# chest_07_15_2017.net
KiCad netlist of a schematic drawn in EAGLE
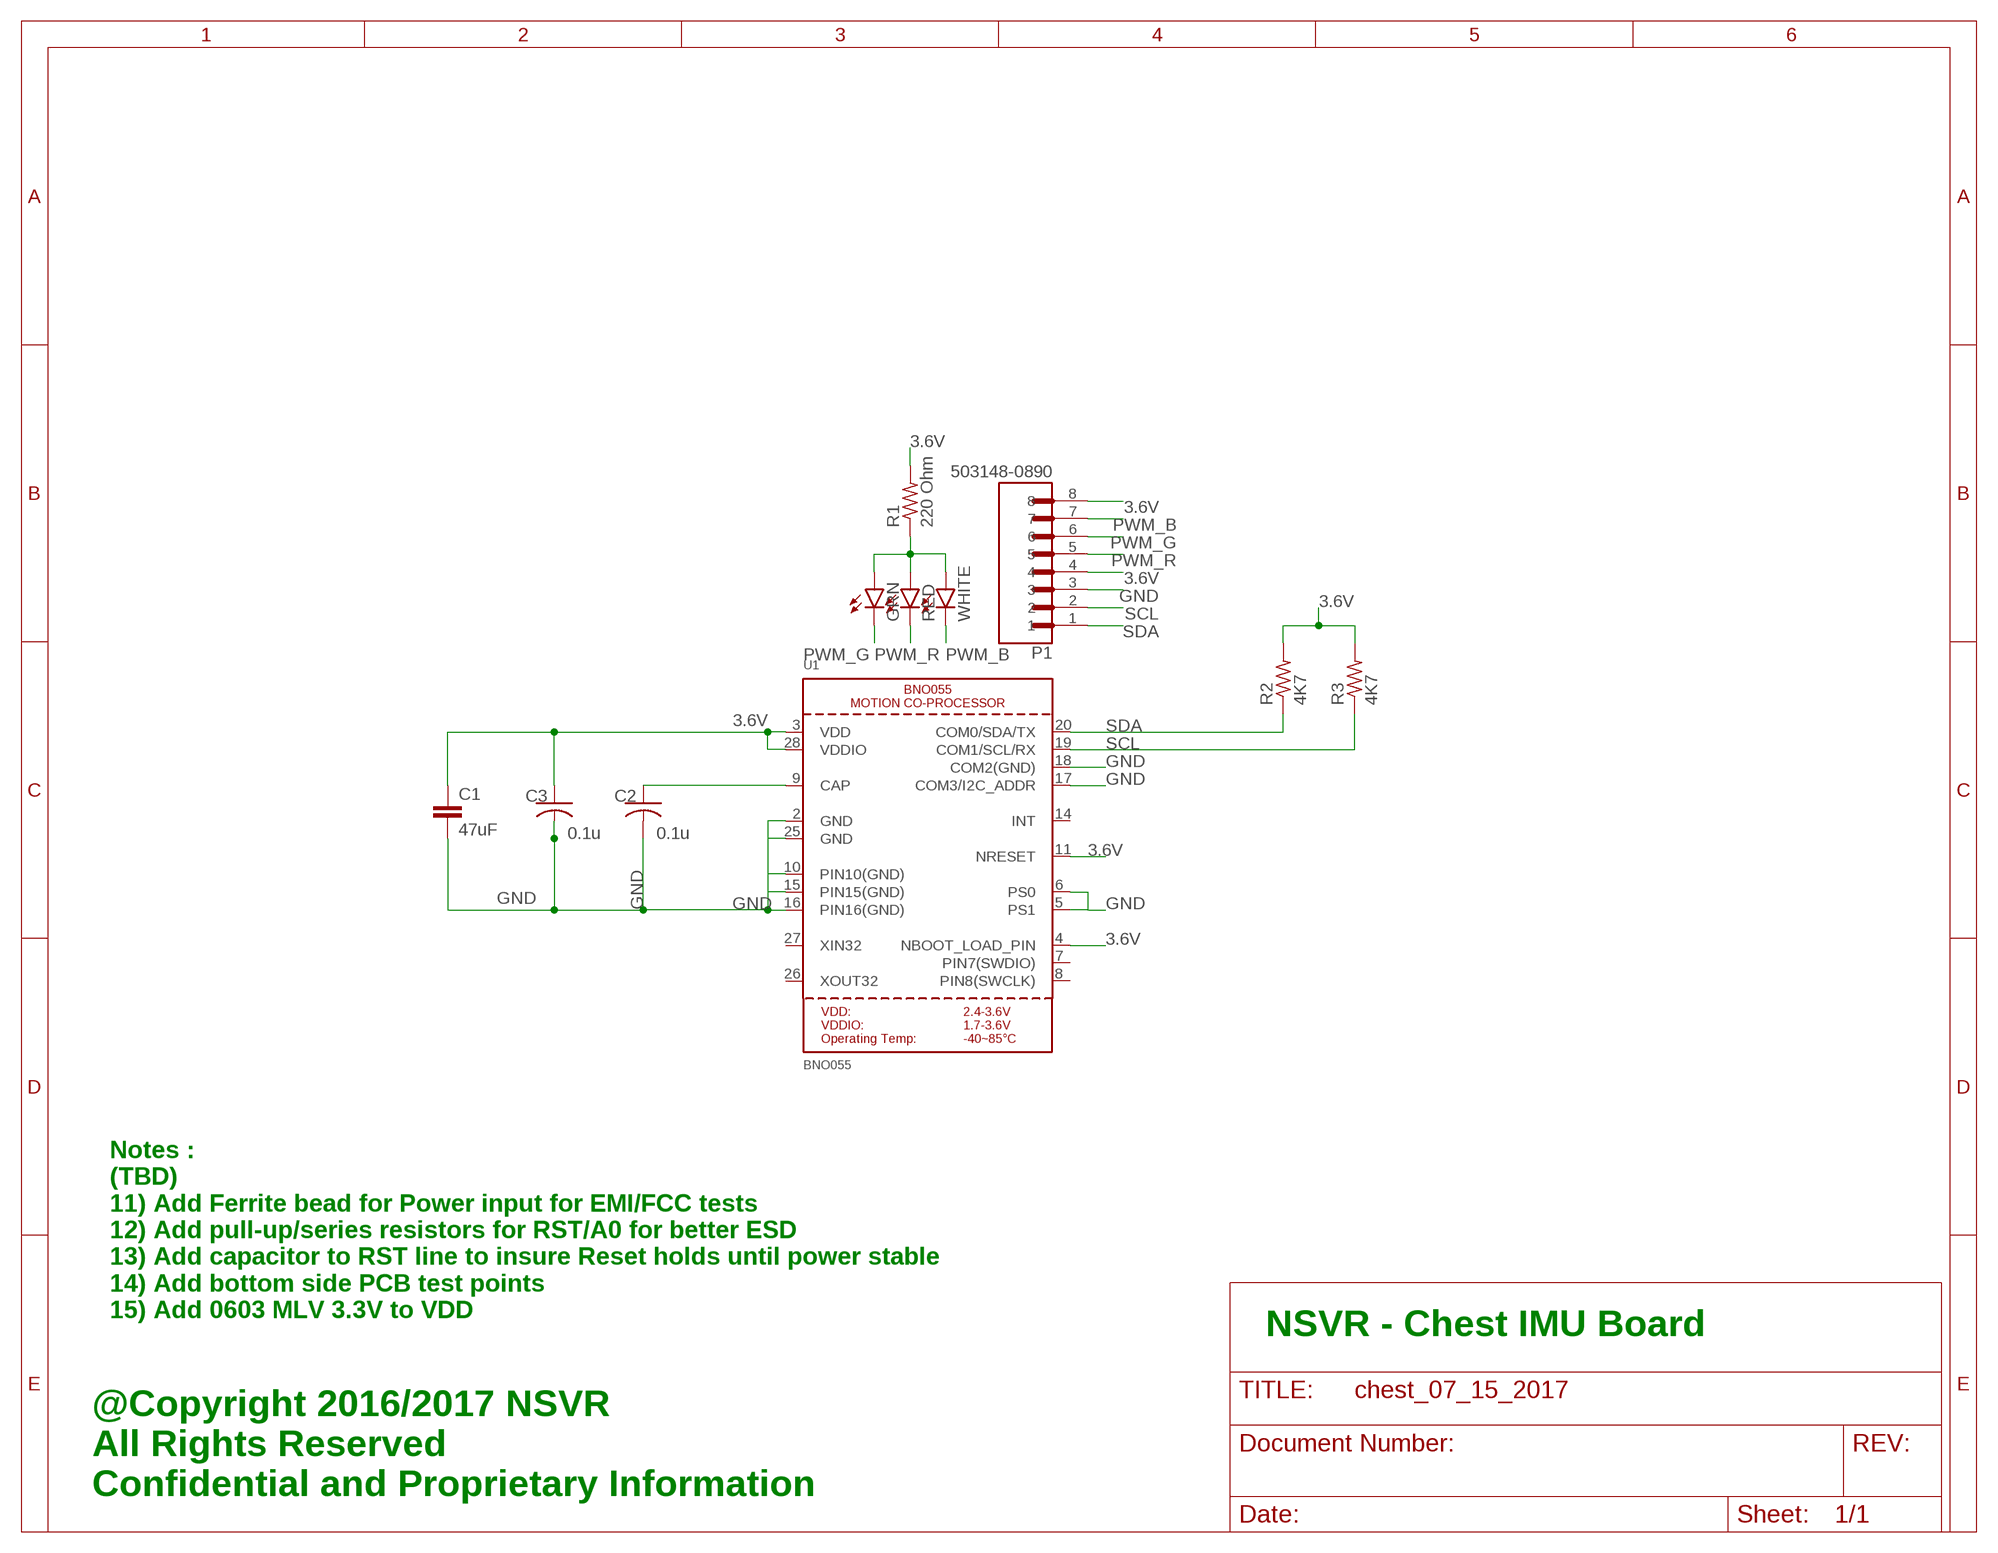
[diagram p0: schematic, sheet 1]

(export (version "E")
  (design (tool "Eeschema 10.0.6"))
  (components
    (comp (ref "C1")
      (value "47uF")
      (footprint "eagle-import:1206")
      (libsource (lib "eagle-import") (part "CAP1206"))
    )
    (comp (ref "C2")
      (value "0.1u")
      (footprint "eagle-import:C0402")
      (libsource (lib "eagle-import") (part "C-USC0402"))
    )
    (comp (ref "C3")
      (value "0.1u")
      (footprint "eagle-import:C0402")
      (libsource (lib "eagle-import") (part "C-USC0402"))
    )
    (comp (ref "GRN")
      (value "LED0603")
      (footprint "eagle-import:LED-0603")
      (libsource (lib "eagle-import") (part "LED0603"))
    )
    (comp (ref "P1")
      (value "503148-0890")
      (footprint "eagle-import:MOLEX_503148-0890")
      (fields (field (name "MF") "Molex"))
      (libsource (lib "eagle-import") (part "503148-0890"))
    )
    (comp (ref "R1")
      (value "220 Ohm")
      (footprint "eagle-import:R0402")
      (libsource (lib "eagle-import") (part "R-US_R0402"))
    )
    (comp (ref "R2")
      (value "4K7")
      (footprint "eagle-import:R0402")
      (libsource (lib "eagle-import") (part "R-US_R0402"))
    )
    (comp (ref "R3")
      (value "4K7")
      (footprint "eagle-import:R0402")
      (libsource (lib "eagle-import") (part "R-US_R0402"))
    )
    (comp (ref "RED")
      (value "LED0603")
      (footprint "eagle-import:LED-0603")
      (libsource (lib "eagle-import") (part "LED0603"))
    )
    (comp (ref "U1")
      (value "BNO055")
      (footprint "eagle-import:BNO055")
      (libsource (lib "eagle-import") (part "BNO055"))
    )
    (comp (ref "WHITE")
      (value "LED0603")
      (footprint "eagle-import:LED-0603")
      (libsource (lib "eagle-import") (part "LED0603"))
    )
  )
  (nets
    (net (code "1") (name "/3.6V") (class "Default")
      (node (ref "C1") (pin "1") (pinfunction "1_1") (pintype "passive"))
      (node (ref "C3") (pin "1") (pinfunction "1_1") (pintype "passive"))
      (node (ref "P1") (pin "4") (pinfunction "4_4") (pintype "passive"))
      (node (ref "P1") (pin "8") (pinfunction "8_8") (pintype "passive"))
      (node (ref "R1") (pin "2") (pinfunction "2_2") (pintype "passive"))
      (node (ref "R2") (pin "2") (pinfunction "2_2") (pintype "passive"))
      (node (ref "R3") (pin "2") (pinfunction "2_2") (pintype "passive"))
      (node (ref "U1") (pin "11") (pinfunction "NRESET_11") (pintype "bidirectional"))
      (node (ref "U1") (pin "28") (pinfunction "VDDIO_28") (pintype "power_in"))
      (node (ref "U1") (pin "3") (pinfunction "VDD_3") (pintype "power_in"))
      (node (ref "U1") (pin "4") (pinfunction "NBOOT_LOAD_PIN_4") (pintype "bidirectional"))
    )
    (net (code "2") (name "/GND") (class "Default")
      (node (ref "C1") (pin "2") (pinfunction "2_2") (pintype "passive"))
      (node (ref "C2") (pin "2") (pinfunction "2_2") (pintype "passive"))
      (node (ref "C3") (pin "2") (pinfunction "2_2") (pintype "passive"))
      (node (ref "P1") (pin "3") (pinfunction "3_3") (pintype "passive"))
      (node (ref "U1") (pin "10") (pinfunction "PIN10(GND)_10") (pintype "bidirectional"))
      (node (ref "U1") (pin "15") (pinfunction "PIN15(GND)_15") (pintype "bidirectional"))
      (node (ref "U1") (pin "16") (pinfunction "PIN16(GND)_16") (pintype "bidirectional"))
      (node (ref "U1") (pin "17") (pinfunction "COM3/I2C_ADDR_17") (pintype "bidirectional"))
      (node (ref "U1") (pin "18") (pinfunction "COM2(GND)_18") (pintype "bidirectional"))
      (node (ref "U1") (pin "2") (pinfunction "GND_2") (pintype "power_in"))
      (node (ref "U1") (pin "25") (pinfunction "GND_25") (pintype "power_in"))
      (node (ref "U1") (pin "5") (pinfunction "PS1_5") (pintype "input"))
      (node (ref "U1") (pin "6") (pinfunction "PS0_6") (pintype "input"))
    )
    (net (code "3") (name "/PWM_B") (class "Default")
      (node (ref "P1") (pin "7") (pinfunction "7_7") (pintype "passive"))
      (node (ref "WHITE") (pin "C") (pinfunction "C_C") (pintype "passive"))
    )
    (net (code "4") (name "/PWM_G") (class "Default")
      (node (ref "GRN") (pin "C") (pinfunction "C_C") (pintype "passive"))
      (node (ref "P1") (pin "6") (pinfunction "6_6") (pintype "passive"))
    )
    (net (code "5") (name "/PWM_R") (class "Default")
      (node (ref "P1") (pin "5") (pinfunction "5_5") (pintype "passive"))
      (node (ref "RED") (pin "C") (pinfunction "C_C") (pintype "passive"))
    )
    (net (code "6") (name "/SCL") (class "Default")
      (node (ref "P1") (pin "2") (pinfunction "2_2") (pintype "passive"))
      (node (ref "R3") (pin "1") (pinfunction "1_1") (pintype "passive"))
      (node (ref "U1") (pin "19") (pinfunction "COM1/SCL/RX_19") (pintype "bidirectional"))
    )
    (net (code "7") (name "/SDA") (class "Default")
      (node (ref "P1") (pin "1") (pinfunction "1_1") (pintype "passive"))
      (node (ref "R2") (pin "1") (pinfunction "1_1") (pintype "passive"))
      (node (ref "U1") (pin "20") (pinfunction "COM0/SDA/TX_20") (pintype "bidirectional"))
    )
    (net (code "8") (name "Net-(GRN-PadA)") (class "Default")
      (node (ref "GRN") (pin "A") (pinfunction "A_A") (pintype "passive"))
      (node (ref "R1") (pin "1") (pinfunction "1_1") (pintype "passive"))
      (node (ref "RED") (pin "A") (pinfunction "A_A") (pintype "passive"))
      (node (ref "WHITE") (pin "A") (pinfunction "A_A") (pintype "passive"))
    )
    (net (code "9") (name "Net-(U1-CAP)") (class "Default")
      (node (ref "C2") (pin "1") (pinfunction "1_1") (pintype "passive"))
      (node (ref "U1") (pin "9") (pinfunction "CAP_9") (pintype "passive"))
    )
    (net (code "10") (name "unconnected-(U1-INT-Pad14)") (class "Default")
      (node (ref "U1") (pin "14") (pinfunction "INT_14") (pintype "output"))
    )
    (net (code "11") (name "unconnected-(U1-PIN7(SWDIO)-Pad7)") (class "Default")
      (node (ref "U1") (pin "7") (pinfunction "PIN7(SWDIO)_7") (pintype "bidirectional"))
    )
    (net (code "12") (name "unconnected-(U1-PIN8(SWCLK)-Pad8)") (class "Default")
      (node (ref "U1") (pin "8") (pinfunction "PIN8(SWCLK)_8") (pintype "bidirectional"))
    )
    (net (code "13") (name "unconnected-(U1-XIN32-Pad27)") (class "Default")
      (node (ref "U1") (pin "27") (pinfunction "XIN32_27") (pintype "input"))
    )
    (net (code "14") (name "unconnected-(U1-XOUT32-Pad26)") (class "Default")
      (node (ref "U1") (pin "26") (pinfunction "XOUT32_26") (pintype "output"))
    )
  )
)
